# bot_schem_rev4.net
KiCad netlist of a schematic drawn in Altium Designer
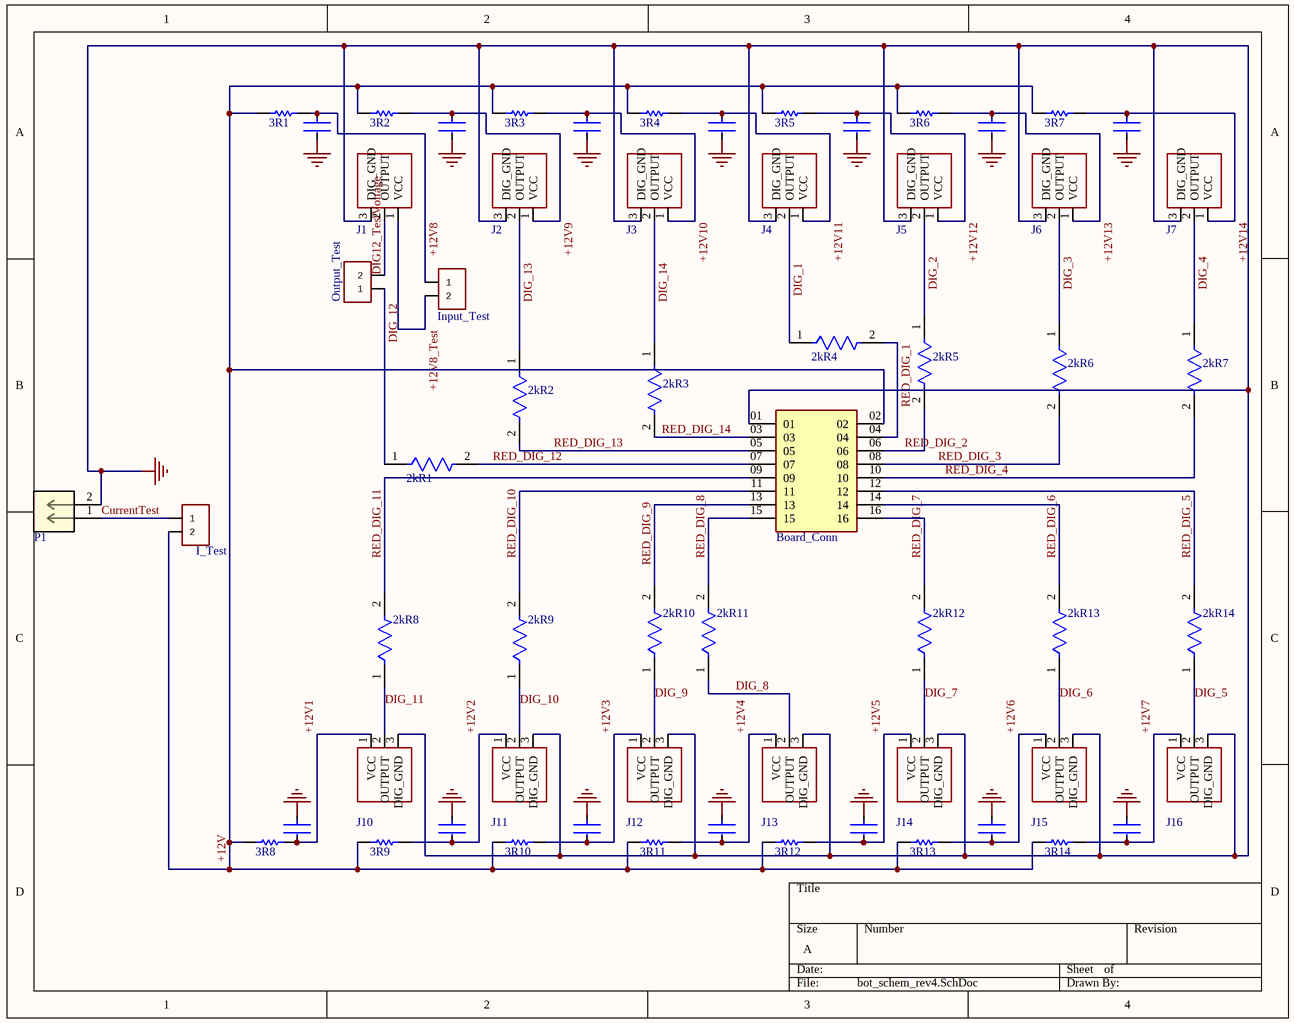
[diagram p0: bot_schem_rev4.SchDoc]

(export (version "E")
  (design (tool "Eeschema 10.0.6"))
  (components
    (comp (ref "2kR1")
      (value "CRCW06031K80FKEA")
      (footprint "2kOhm")
      (description "Res Thick Film 0603 1.8K Ohm 1% 1/10W ±100ppm/°C Molded SMD Paper T/R")
      (fields (field (name "MANUFACTURER") "Vishay") (field (name "TOLERANCE") "1%"))
      (libsource (lib "ps_schlib") (part "CRCW06031K80FKEA"))
    )
    (comp (ref "2kR2")
      (value "CRCW06031K80FKEA")
      (footprint "2kOhm")
      (description "Res Thick Film 0603 1.8K Ohm 1% 1/10W ±100ppm/°C Molded SMD Paper T/R")
      (fields (field (name "MANUFACTURER") "Vishay") (field (name "TOLERANCE") "1%"))
      (libsource (lib "ps_schlib") (part "CRCW06031K80FKEA"))
    )
    (comp (ref "2kR3")
      (value "CRCW06031K80FKEA")
      (footprint "2kOhm")
      (description "Res Thick Film 0603 1.8K Ohm 1% 1/10W ±100ppm/°C Molded SMD Paper T/R")
      (fields (field (name "MANUFACTURER") "Vishay") (field (name "TOLERANCE") "1%"))
      (libsource (lib "ps_schlib") (part "CRCW06031K80FKEA"))
    )
    (comp (ref "2kR4")
      (value "CRCW06031K80FKEA")
      (footprint "2kOhm")
      (description "Res Thick Film 0603 1.8K Ohm 1% 1/10W ±100ppm/°C Molded SMD Paper T/R")
      (fields (field (name "MANUFACTURER") "Vishay") (field (name "TOLERANCE") "1%"))
      (libsource (lib "ps_schlib") (part "CRCW06031K80FKEA"))
    )
    (comp (ref "2kR5")
      (value "CRCW06031K80FKEA")
      (footprint "2kOhm")
      (description "Res Thick Film 0603 1.8K Ohm 1% 1/10W ±100ppm/°C Molded SMD Paper T/R")
      (fields (field (name "MANUFACTURER") "Vishay") (field (name "TOLERANCE") "1%"))
      (libsource (lib "ps_schlib") (part "CRCW06031K80FKEA"))
    )
    (comp (ref "2kR6")
      (value "CRCW06031K80FKEA")
      (footprint "2kOhm")
      (description "Res Thick Film 0603 1.8K Ohm 1% 1/10W ±100ppm/°C Molded SMD Paper T/R")
      (fields (field (name "MANUFACTURER") "Vishay") (field (name "TOLERANCE") "1%"))
      (libsource (lib "ps_schlib") (part "CRCW06031K80FKEA"))
    )
    (comp (ref "2kR7")
      (value "CRCW06031K80FKEA")
      (footprint "2kOhm")
      (description "Res Thick Film 0603 1.8K Ohm 1% 1/10W ±100ppm/°C Molded SMD Paper T/R")
      (fields (field (name "MANUFACTURER") "Vishay") (field (name "TOLERANCE") "1%"))
      (libsource (lib "ps_schlib") (part "CRCW06031K80FKEA"))
    )
    (comp (ref "2kR8")
      (value "CRCW06031K80FKEA")
      (footprint "2kOhm")
      (description "Res Thick Film 0603 1.8K Ohm 1% 1/10W ±100ppm/°C Molded SMD Paper T/R")
      (fields (field (name "MANUFACTURER") "Vishay") (field (name "TOLERANCE") "1%"))
      (libsource (lib "ps_schlib") (part "CRCW06031K80FKEA"))
    )
    (comp (ref "2kR9")
      (value "CRCW06031K80FKEA")
      (footprint "2kOhm")
      (description "Res Thick Film 0603 1.8K Ohm 1% 1/10W ±100ppm/°C Molded SMD Paper T/R")
      (fields (field (name "MANUFACTURER") "Vishay") (field (name "TOLERANCE") "1%"))
      (libsource (lib "ps_schlib") (part "CRCW06031K80FKEA"))
    )
    (comp (ref "2kR10")
      (value "CRCW06031K80FKEA")
      (footprint "2kOhm")
      (description "Res Thick Film 0603 1.8K Ohm 1% 1/10W ±100ppm/°C Molded SMD Paper T/R")
      (fields (field (name "MANUFACTURER") "Vishay") (field (name "TOLERANCE") "1%"))
      (libsource (lib "ps_schlib") (part "CRCW06031K80FKEA"))
    )
    (comp (ref "2kR11")
      (value "CRCW06031K80FKEA")
      (footprint "2kOhm")
      (description "Res Thick Film 0603 1.8K Ohm 1% 1/10W ±100ppm/°C Molded SMD Paper T/R")
      (fields (field (name "MANUFACTURER") "Vishay") (field (name "TOLERANCE") "1%"))
      (libsource (lib "ps_schlib") (part "CRCW06031K80FKEA"))
    )
    (comp (ref "2kR12")
      (value "CRCW06031K80FKEA")
      (footprint "2kOhm")
      (description "Res Thick Film 0603 1.8K Ohm 1% 1/10W ±100ppm/°C Molded SMD Paper T/R")
      (fields (field (name "MANUFACTURER") "Vishay") (field (name "TOLERANCE") "1%"))
      (libsource (lib "ps_schlib") (part "CRCW06031K80FKEA"))
    )
    (comp (ref "2kR13")
      (value "CRCW06031K80FKEA")
      (footprint "2kOhm")
      (description "Res Thick Film 0603 1.8K Ohm 1% 1/10W ±100ppm/°C Molded SMD Paper T/R")
      (fields (field (name "MANUFACTURER") "Vishay") (field (name "TOLERANCE") "1%"))
      (libsource (lib "ps_schlib") (part "CRCW06031K80FKEA"))
    )
    (comp (ref "2kR14")
      (value "CRCW06031K80FKEA")
      (footprint "2kOhm")
      (description "Res Thick Film 0603 1.8K Ohm 1% 1/10W ±100ppm/°C Molded SMD Paper T/R")
      (fields (field (name "MANUFACTURER") "Vishay") (field (name "TOLERANCE") "1%"))
      (libsource (lib "ps_schlib") (part "CRCW06031K80FKEA"))
    )
    (comp (ref "3R1")
      (value "ERJ-2BQJR30X")
      (footprint "03 Ohm")
      (description "RES 0.3 OHM 5% 1/6W 0402")
      (fields (field (name "MANUFACTURER") "Panasonic") (field (name "TOLERANCE") "5%"))
      (libsource (lib "ps_schlib") (part "ERJ-2BQJR30X"))
    )
    (comp (ref "3R2")
      (value "ERJ-2BQJR30X")
      (footprint "03 Ohm")
      (description "RES 0.3 OHM 5% 1/6W 0402")
      (fields (field (name "MANUFACTURER") "Panasonic") (field (name "TOLERANCE") "5%"))
      (libsource (lib "ps_schlib") (part "ERJ-2BQJR30X"))
    )
    (comp (ref "3R3")
      (value "ERJ-2BQJR30X")
      (footprint "03 Ohm")
      (description "RES 0.3 OHM 5% 1/6W 0402")
      (fields (field (name "MANUFACTURER") "Panasonic") (field (name "TOLERANCE") "5%"))
      (libsource (lib "ps_schlib") (part "ERJ-2BQJR30X"))
    )
    (comp (ref "3R4")
      (value "ERJ-2BQJR30X")
      (footprint "03 Ohm")
      (description "RES 0.3 OHM 5% 1/6W 0402")
      (fields (field (name "MANUFACTURER") "Panasonic") (field (name "TOLERANCE") "5%"))
      (libsource (lib "ps_schlib") (part "ERJ-2BQJR30X"))
    )
    (comp (ref "3R5")
      (value "ERJ-2BQJR30X")
      (footprint "03 Ohm")
      (description "RES 0.3 OHM 5% 1/6W 0402")
      (fields (field (name "MANUFACTURER") "Panasonic") (field (name "TOLERANCE") "5%"))
      (libsource (lib "ps_schlib") (part "ERJ-2BQJR30X"))
    )
    (comp (ref "3R6")
      (value "ERJ-2BQJR30X")
      (footprint "03 Ohm")
      (description "RES 0.3 OHM 5% 1/6W 0402")
      (fields (field (name "MANUFACTURER") "Panasonic") (field (name "TOLERANCE") "5%"))
      (libsource (lib "ps_schlib") (part "ERJ-2BQJR30X"))
    )
    (comp (ref "3R7")
      (value "ERJ-2BQJR30X")
      (footprint "03 Ohm")
      (description "RES 0.3 OHM 5% 1/6W 0402")
      (fields (field (name "MANUFACTURER") "Panasonic") (field (name "TOLERANCE") "5%"))
      (libsource (lib "ps_schlib") (part "ERJ-2BQJR30X"))
    )
    (comp (ref "3R8")
      (value "ERJ-2BQJR30X")
      (footprint "03 Ohm")
      (description "RES 0.3 OHM 5% 1/6W 0402")
      (fields (field (name "MANUFACTURER") "Panasonic") (field (name "TOLERANCE") "5%"))
      (libsource (lib "ps_schlib") (part "ERJ-2BQJR30X"))
    )
    (comp (ref "3R9")
      (value "ERJ-2BQJR30X")
      (footprint "03 Ohm")
      (description "RES 0.3 OHM 5% 1/6W 0402")
      (fields (field (name "MANUFACTURER") "Panasonic") (field (name "TOLERANCE") "5%"))
      (libsource (lib "ps_schlib") (part "ERJ-2BQJR30X"))
    )
    (comp (ref "3R10")
      (value "ERJ-2BQJR30X")
      (footprint "03 Ohm")
      (description "RES 0.3 OHM 5% 1/6W 0402")
      (fields (field (name "MANUFACTURER") "Panasonic") (field (name "TOLERANCE") "5%"))
      (libsource (lib "ps_schlib") (part "ERJ-2BQJR30X"))
    )
    (comp (ref "3R11")
      (value "ERJ-2BQJR30X")
      (footprint "03 Ohm")
      (description "RES 0.3 OHM 5% 1/6W 0402")
      (fields (field (name "MANUFACTURER") "Panasonic") (field (name "TOLERANCE") "5%"))
      (libsource (lib "ps_schlib") (part "ERJ-2BQJR30X"))
    )
    (comp (ref "3R12")
      (value "ERJ-2BQJR30X")
      (footprint "03 Ohm")
      (description "RES 0.3 OHM 5% 1/6W 0402")
      (fields (field (name "MANUFACTURER") "Panasonic") (field (name "TOLERANCE") "5%"))
      (libsource (lib "ps_schlib") (part "ERJ-2BQJR30X"))
    )
    (comp (ref "3R13")
      (value "ERJ-2BQJR30X")
      (footprint "03 Ohm")
      (description "RES 0.3 OHM 5% 1/6W 0402")
      (fields (field (name "MANUFACTURER") "Panasonic") (field (name "TOLERANCE") "5%"))
      (libsource (lib "ps_schlib") (part "ERJ-2BQJR30X"))
    )
    (comp (ref "3R14")
      (value "ERJ-2BQJR30X")
      (footprint "03 Ohm")
      (description "RES 0.3 OHM 5% 1/6W 0402")
      (fields (field (name "MANUFACTURER") "Panasonic") (field (name "TOLERANCE") "5%"))
      (libsource (lib "ps_schlib") (part "ERJ-2BQJR30X"))
    )
    (comp (ref "Board_Conn")
      (value "HW-08-11-F-D-511-SM")
      (footprint "16 pin receiver")
      (libsource (lib "ps_schlib") (part "HW-08-11-F-D-507-SM"))
    )
    (comp (ref "C1")
      (value "C0805C104K5RACTU")
      (footprint "100nF")
      (description "Cap Ceramic 0.1uF 50V X7R 10% SMD 2.0 x 1.2 mm 125 C Paper T/R")
      (fields (field (name "MANUFACTURER") "KEMET") (field (name "TOLERANCE") "10%"))
      (libsource (lib "ps_schlib") (part "C0805C104K5RACTU"))
    )
    (comp (ref "C2")
      (value "C0805C104K5RACTU")
      (footprint "100nF")
      (description "Cap Ceramic 0.1uF 50V X7R 10% SMD 2.0 x 1.2 mm 125 C Paper T/R")
      (fields (field (name "MANUFACTURER") "KEMET") (field (name "TOLERANCE") "10%"))
      (libsource (lib "ps_schlib") (part "C0805C104K5RACTU"))
    )
    (comp (ref "C3")
      (value "C0805C104K5RACTU")
      (footprint "100nF")
      (description "Cap Ceramic 0.1uF 50V X7R 10% SMD 2.0 x 1.2 mm 125 C Paper T/R")
      (fields (field (name "MANUFACTURER") "KEMET") (field (name "TOLERANCE") "10%"))
      (libsource (lib "ps_schlib") (part "C0805C104K5RACTU"))
    )
    (comp (ref "C4")
      (value "C0805C104K5RACTU")
      (footprint "100nF")
      (description "Cap Ceramic 0.1uF 50V X7R 10% SMD 2.0 x 1.2 mm 125 C Paper T/R")
      (fields (field (name "MANUFACTURER") "KEMET") (field (name "TOLERANCE") "10%"))
      (libsource (lib "ps_schlib") (part "C0805C104K5RACTU"))
    )
    (comp (ref "C5")
      (value "C0805C104K5RACTU")
      (footprint "100nF")
      (description "Cap Ceramic 0.1uF 50V X7R 10% SMD 2.0 x 1.2 mm 125 C Paper T/R")
      (fields (field (name "MANUFACTURER") "KEMET") (field (name "TOLERANCE") "10%"))
      (libsource (lib "ps_schlib") (part "C0805C104K5RACTU"))
    )
    (comp (ref "C6")
      (value "C0805C104K5RACTU")
      (footprint "100nF")
      (description "Cap Ceramic 0.1uF 50V X7R 10% SMD 2.0 x 1.2 mm 125 C Paper T/R")
      (fields (field (name "MANUFACTURER") "KEMET") (field (name "TOLERANCE") "10%"))
      (libsource (lib "ps_schlib") (part "C0805C104K5RACTU"))
    )
    (comp (ref "C7")
      (value "C0805C104K5RACTU")
      (footprint "100nF")
      (description "Cap Ceramic 0.1uF 50V X7R 10% SMD 2.0 x 1.2 mm 125 C Paper T/R")
      (fields (field (name "MANUFACTURER") "KEMET") (field (name "TOLERANCE") "10%"))
      (libsource (lib "ps_schlib") (part "C0805C104K5RACTU"))
    )
    (comp (ref "C8")
      (value "C0805C104K5RACTU")
      (footprint "100nF")
      (description "Cap Ceramic 0.1uF 50V X7R 10% SMD 2.0 x 1.2 mm 125 C Paper T/R")
      (fields (field (name "MANUFACTURER") "KEMET") (field (name "TOLERANCE") "10%"))
      (libsource (lib "ps_schlib") (part "C0805C104K5RACTU"))
    )
    (comp (ref "C9")
      (value "C0805C104K5RACTU")
      (footprint "100nF")
      (description "Cap Ceramic 0.1uF 50V X7R 10% SMD 2.0 x 1.2 mm 125 C Paper T/R")
      (fields (field (name "MANUFACTURER") "KEMET") (field (name "TOLERANCE") "10%"))
      (libsource (lib "ps_schlib") (part "C0805C104K5RACTU"))
    )
    (comp (ref "C10")
      (value "C0805C104K5RACTU")
      (footprint "100nF")
      (description "Cap Ceramic 0.1uF 50V X7R 10% SMD 2.0 x 1.2 mm 125 C Paper T/R")
      (fields (field (name "MANUFACTURER") "KEMET") (field (name "TOLERANCE") "10%"))
      (libsource (lib "ps_schlib") (part "C0805C104K5RACTU"))
    )
    (comp (ref "C11")
      (value "C0805C104K5RACTU")
      (footprint "100nF")
      (description "Cap Ceramic 0.1uF 50V X7R 10% SMD 2.0 x 1.2 mm 125 C Paper T/R")
      (fields (field (name "MANUFACTURER") "KEMET") (field (name "TOLERANCE") "10%"))
      (libsource (lib "ps_schlib") (part "C0805C104K5RACTU"))
    )
    (comp (ref "C12")
      (value "C0805C104K5RACTU")
      (footprint "100nF")
      (description "Cap Ceramic 0.1uF 50V X7R 10% SMD 2.0 x 1.2 mm 125 C Paper T/R")
      (fields (field (name "MANUFACTURER") "KEMET") (field (name "TOLERANCE") "10%"))
      (libsource (lib "ps_schlib") (part "C0805C104K5RACTU"))
    )
    (comp (ref "C13")
      (value "C0805C104K5RACTU")
      (footprint "100nF")
      (description "Cap Ceramic 0.1uF 50V X7R 10% SMD 2.0 x 1.2 mm 125 C Paper T/R")
      (fields (field (name "MANUFACTURER") "KEMET") (field (name "TOLERANCE") "10%"))
      (libsource (lib "ps_schlib") (part "C0805C104K5RACTU"))
    )
    (comp (ref "C14")
      (value "C0805C104K5RACTU")
      (footprint "100nF")
      (description "Cap Ceramic 0.1uF 50V X7R 10% SMD 2.0 x 1.2 mm 125 C Paper T/R")
      (fields (field (name "MANUFACTURER") "KEMET") (field (name "TOLERANCE") "10%"))
      (libsource (lib "ps_schlib") (part "C0805C104K5RACTU"))
    )
    (comp (ref "Input_Test")
      (value "PRPC001DFAN-RC")
      (footprint "PRPC001DFAN-RC")
      (description "Conn Header Vert 2POS")
      (fields (field (name "MANUFACTURER") "Sullins"))
      (libsource (lib "ps_schlib") (part "PRPC001DFAN-RC"))
    )
    (comp (ref "I_Test")
      (value "PRPC001DFAN-RC")
      (footprint "PRPC001DFAN-RC")
      (description "Conn Header Vert 2POS")
      (fields (field (name "MANUFACTURER") "Sullins"))
      (libsource (lib "ps_schlib") (part "PRPC001DFAN-RC"))
    )
    (comp (ref "J1")
      (value "IF-D95T")
      (footprint "IF-D95")
      (description "DETECTOR PHOTOLOGIC TTL/CMOS")
      (fields (field (name "MANUFACTURER") "Industrial Fiber Optics"))
      (libsource (lib "ps_schlib") (part "IF-D95T"))
    )
    (comp (ref "J2")
      (value "IF-D95T")
      (footprint "IF-D95")
      (description "DETECTOR PHOTOLOGIC TTL/CMOS")
      (fields (field (name "MANUFACTURER") "Industrial Fiber Optics"))
      (libsource (lib "ps_schlib") (part "IF-D95T"))
    )
    (comp (ref "J3")
      (value "IF-D95T")
      (footprint "IF-D95")
      (description "DETECTOR PHOTOLOGIC TTL/CMOS")
      (fields (field (name "MANUFACTURER") "Industrial Fiber Optics"))
      (libsource (lib "ps_schlib") (part "IF-D95T"))
    )
    (comp (ref "J4")
      (value "IF-D95T")
      (footprint "IF-D95")
      (description "DETECTOR PHOTOLOGIC TTL/CMOS")
      (fields (field (name "MANUFACTURER") "Industrial Fiber Optics"))
      (libsource (lib "ps_schlib") (part "IF-D95T"))
    )
    (comp (ref "J5")
      (value "IF-D95T")
      (footprint "IF-D95")
      (description "DETECTOR PHOTOLOGIC TTL/CMOS")
      (fields (field (name "MANUFACTURER") "Industrial Fiber Optics"))
      (libsource (lib "ps_schlib") (part "IF-D95T"))
    )
    (comp (ref "J6")
      (value "IF-D95T")
      (footprint "IF-D95")
      (description "DETECTOR PHOTOLOGIC TTL/CMOS")
      (fields (field (name "MANUFACTURER") "Industrial Fiber Optics"))
      (libsource (lib "ps_schlib") (part "IF-D95T"))
    )
    (comp (ref "J7")
      (value "IF-D95T")
      (footprint "IF-D95")
      (description "DETECTOR PHOTOLOGIC TTL/CMOS")
      (fields (field (name "MANUFACTURER") "Industrial Fiber Optics"))
      (libsource (lib "ps_schlib") (part "IF-D95T"))
    )
    (comp (ref "J10")
      (value "IF-D95T")
      (footprint "IF-D95")
      (description "DETECTOR PHOTOLOGIC TTL/CMOS")
      (fields (field (name "MANUFACTURER") "Industrial Fiber Optics"))
      (libsource (lib "ps_schlib") (part "IF-D95T"))
    )
    (comp (ref "J11")
      (value "IF-D95T")
      (footprint "IF-D95")
      (description "DETECTOR PHOTOLOGIC TTL/CMOS")
      (fields (field (name "MANUFACTURER") "Industrial Fiber Optics"))
      (libsource (lib "ps_schlib") (part "IF-D95T"))
    )
    (comp (ref "J12")
      (value "IF-D95T")
      (footprint "IF-D95")
      (description "DETECTOR PHOTOLOGIC TTL/CMOS")
      (fields (field (name "MANUFACTURER") "Industrial Fiber Optics"))
      (libsource (lib "ps_schlib") (part "IF-D95T"))
    )
    (comp (ref "J13")
      (value "IF-D95T")
      (footprint "IF-D95")
      (description "DETECTOR PHOTOLOGIC TTL/CMOS")
      (fields (field (name "MANUFACTURER") "Industrial Fiber Optics"))
      (libsource (lib "ps_schlib") (part "IF-D95T"))
    )
    (comp (ref "J14")
      (value "IF-D95T")
      (footprint "IF-D95")
      (description "DETECTOR PHOTOLOGIC TTL/CMOS")
      (fields (field (name "MANUFACTURER") "Industrial Fiber Optics"))
      (libsource (lib "ps_schlib") (part "IF-D95T"))
    )
    (comp (ref "J15")
      (value "IF-D95T")
      (footprint "IF-D95")
      (description "DETECTOR PHOTOLOGIC TTL/CMOS")
      (fields (field (name "MANUFACTURER") "Industrial Fiber Optics"))
      (libsource (lib "ps_schlib") (part "IF-D95T"))
    )
    (comp (ref "J16")
      (value "IF-D95T")
      (footprint "IF-D95")
      (description "DETECTOR PHOTOLOGIC TTL/CMOS")
      (fields (field (name "MANUFACTURER") "Industrial Fiber Optics"))
      (libsource (lib "ps_schlib") (part "IF-D95T"))
    )
    (comp (ref "Output_Test")
      (value "PRPC001DFAN-RC")
      (footprint "PRPC001DFAN-RC")
      (description "Conn Header Vert 2POS")
      (fields (field (name "MANUFACTURER") "Sullins"))
      (libsource (lib "ps_schlib") (part "PRPC001DFAN-RC"))
    )
    (comp (ref "P1")
      (value "1054311102")
      (footprint "CONN_1054311102_MOL")
      (fields (field (name "MANUFACTURER") "Molex"))
      (libsource (lib "ps_schlib") (part "1054311102"))
    )
  )
  (nets
    (net (code "1") (name "/+12V") (class "Default")
      (node (ref "3R1") (pin "1") (pinfunction "1_1") (pintype "passive"))
      (node (ref "3R10") (pin "1") (pinfunction "1_1") (pintype "passive"))
      (node (ref "3R11") (pin "1") (pinfunction "1_1") (pintype "passive"))
      (node (ref "3R12") (pin "1") (pinfunction "1_1") (pintype "passive"))
      (node (ref "3R13") (pin "1") (pinfunction "1_1") (pintype "passive"))
      (node (ref "3R14") (pin "1") (pinfunction "1_1") (pintype "passive"))
      (node (ref "3R2") (pin "1") (pinfunction "1_1") (pintype "passive"))
      (node (ref "3R3") (pin "1") (pinfunction "1_1") (pintype "passive"))
      (node (ref "3R4") (pin "1") (pinfunction "1_1") (pintype "passive"))
      (node (ref "3R5") (pin "1") (pinfunction "1_1") (pintype "passive"))
      (node (ref "3R6") (pin "1") (pinfunction "1_1") (pintype "passive"))
      (node (ref "3R7") (pin "1") (pinfunction "1_1") (pintype "passive"))
      (node (ref "3R8") (pin "1") (pinfunction "1_1") (pintype "passive"))
      (node (ref "3R9") (pin "1") (pinfunction "1_1") (pintype "passive"))
      (node (ref "Board_Conn") (pin "02") (pinfunction "02_02") (pintype "passive"))
      (node (ref "I_Test") (pin "2") (pinfunction "2_2") (pintype "passive"))
    )
    (net (code "2") (name "/+12V1") (class "Default")
      (node (ref "3R8") (pin "2") (pinfunction "2_2") (pintype "passive"))
      (node (ref "C8") (pin "2") (pinfunction "2_2") (pintype "passive"))
      (node (ref "J10") (pin "1") (pinfunction "VCC_1") (pintype "passive"))
    )
    (net (code "3") (name "/+12V2") (class "Default")
      (node (ref "3R9") (pin "2") (pinfunction "2_2") (pintype "passive"))
      (node (ref "C9") (pin "2") (pinfunction "2_2") (pintype "passive"))
      (node (ref "J11") (pin "1") (pinfunction "VCC_1") (pintype "passive"))
    )
    (net (code "4") (name "/+12V3") (class "Default")
      (node (ref "3R10") (pin "2") (pinfunction "2_2") (pintype "passive"))
      (node (ref "C10") (pin "2") (pinfunction "2_2") (pintype "passive"))
      (node (ref "J12") (pin "1") (pinfunction "VCC_1") (pintype "passive"))
    )
    (net (code "5") (name "/+12V4") (class "Default")
      (node (ref "3R11") (pin "2") (pinfunction "2_2") (pintype "passive"))
      (node (ref "C11") (pin "2") (pinfunction "2_2") (pintype "passive"))
      (node (ref "J13") (pin "1") (pinfunction "VCC_1") (pintype "passive"))
    )
    (net (code "6") (name "/+12V5") (class "Default")
      (node (ref "3R12") (pin "2") (pinfunction "2_2") (pintype "passive"))
      (node (ref "C12") (pin "2") (pinfunction "2_2") (pintype "passive"))
      (node (ref "J14") (pin "1") (pinfunction "VCC_1") (pintype "passive"))
    )
    (net (code "7") (name "/+12V6") (class "Default")
      (node (ref "3R13") (pin "2") (pinfunction "2_2") (pintype "passive"))
      (node (ref "C13") (pin "2") (pinfunction "2_2") (pintype "passive"))
      (node (ref "J15") (pin "1") (pinfunction "VCC_1") (pintype "passive"))
    )
    (net (code "8") (name "/+12V7") (class "Default")
      (node (ref "3R14") (pin "2") (pinfunction "2_2") (pintype "passive"))
      (node (ref "C14") (pin "2") (pinfunction "2_2") (pintype "passive"))
      (node (ref "J16") (pin "1") (pinfunction "VCC_1") (pintype "passive"))
    )
    (net (code "9") (name "/+12V8") (class "Default")
      (node (ref "3R1") (pin "2") (pinfunction "2_2") (pintype "passive"))
      (node (ref "C1") (pin "1") (pinfunction "1_1") (pintype "passive"))
      (node (ref "Input_Test") (pin "1") (pinfunction "1_1") (pintype "passive"))
    )
    (net (code "10") (name "/+12V8_Test") (class "Default")
      (node (ref "Input_Test") (pin "2") (pinfunction "2_2") (pintype "passive"))
      (node (ref "J1") (pin "1") (pinfunction "VCC_1") (pintype "passive"))
    )
    (net (code "11") (name "/+12V9") (class "Default")
      (node (ref "3R2") (pin "2") (pinfunction "2_2") (pintype "passive"))
      (node (ref "C2") (pin "1") (pinfunction "1_1") (pintype "passive"))
      (node (ref "J2") (pin "1") (pinfunction "VCC_1") (pintype "passive"))
    )
    (net (code "12") (name "/+12V10") (class "Default")
      (node (ref "3R3") (pin "2") (pinfunction "2_2") (pintype "passive"))
      (node (ref "C3") (pin "1") (pinfunction "1_1") (pintype "passive"))
      (node (ref "J3") (pin "1") (pinfunction "VCC_1") (pintype "passive"))
    )
    (net (code "13") (name "/+12V11") (class "Default")
      (node (ref "3R4") (pin "2") (pinfunction "2_2") (pintype "passive"))
      (node (ref "C4") (pin "1") (pinfunction "1_1") (pintype "passive"))
      (node (ref "J4") (pin "1") (pinfunction "VCC_1") (pintype "passive"))
    )
    (net (code "14") (name "/+12V12") (class "Default")
      (node (ref "3R5") (pin "2") (pinfunction "2_2") (pintype "passive"))
      (node (ref "C5") (pin "1") (pinfunction "1_1") (pintype "passive"))
      (node (ref "J5") (pin "1") (pinfunction "VCC_1") (pintype "passive"))
    )
    (net (code "15") (name "/+12V13") (class "Default")
      (node (ref "3R6") (pin "2") (pinfunction "2_2") (pintype "passive"))
      (node (ref "C6") (pin "1") (pinfunction "1_1") (pintype "passive"))
      (node (ref "J6") (pin "1") (pinfunction "VCC_1") (pintype "passive"))
    )
    (net (code "16") (name "/+12V14") (class "Default")
      (node (ref "3R7") (pin "2") (pinfunction "2_2") (pintype "passive"))
      (node (ref "C7") (pin "1") (pinfunction "1_1") (pintype "passive"))
      (node (ref "J7") (pin "1") (pinfunction "VCC_1") (pintype "passive"))
    )
    (net (code "18") (name "/CurrentTest") (class "Default")
      (node (ref "I_Test") (pin "1") (pinfunction "1_1") (pintype "passive"))
      (node (ref "P1") (pin "1") (pinfunction "1_1") (pintype "passive"))
    )
    (net (code "19") (name "/DIG12_TestVoltage") (class "Default")
      (node (ref "J1") (pin "2") (pinfunction "OUTPUT_2") (pintype "passive"))
      (node (ref "Output_Test") (pin "2") (pinfunction "2_2") (pintype "passive"))
    )
    (net (code "20") (name "/DIG_1") (class "Default")
      (node (ref "2kR4") (pin "1") (pinfunction "1_1") (pintype "passive"))
      (node (ref "J4") (pin "2") (pinfunction "OUTPUT_2") (pintype "passive"))
    )
    (net (code "21") (name "/DIG_2") (class "Default")
      (node (ref "2kR5") (pin "1") (pinfunction "1_1") (pintype "passive"))
      (node (ref "J5") (pin "2") (pinfunction "OUTPUT_2") (pintype "passive"))
    )
    (net (code "22") (name "/DIG_3") (class "Default")
      (node (ref "2kR6") (pin "1") (pinfunction "1_1") (pintype "passive"))
      (node (ref "J6") (pin "2") (pinfunction "OUTPUT_2") (pintype "passive"))
    )
    (net (code "23") (name "/DIG_4") (class "Default")
      (node (ref "2kR7") (pin "1") (pinfunction "1_1") (pintype "passive"))
      (node (ref "J7") (pin "2") (pinfunction "OUTPUT_2") (pintype "passive"))
    )
    (net (code "24") (name "/DIG_5") (class "Default")
      (node (ref "2kR14") (pin "1") (pinfunction "1_1") (pintype "passive"))
      (node (ref "J16") (pin "2") (pinfunction "OUTPUT_2") (pintype "passive"))
    )
    (net (code "25") (name "/DIG_6") (class "Default")
      (node (ref "2kR13") (pin "1") (pinfunction "1_1") (pintype "passive"))
      (node (ref "J15") (pin "2") (pinfunction "OUTPUT_2") (pintype "passive"))
    )
    (net (code "26") (name "/DIG_7") (class "Default")
      (node (ref "2kR12") (pin "1") (pinfunction "1_1") (pintype "passive"))
      (node (ref "J14") (pin "2") (pinfunction "OUTPUT_2") (pintype "passive"))
    )
    (net (code "27") (name "/DIG_8") (class "Default")
      (node (ref "2kR11") (pin "1") (pinfunction "1_1") (pintype "passive"))
      (node (ref "J13") (pin "2") (pinfunction "OUTPUT_2") (pintype "passive"))
    )
    (net (code "28") (name "/DIG_9") (class "Default")
      (node (ref "2kR10") (pin "1") (pinfunction "1_1") (pintype "passive"))
      (node (ref "J12") (pin "2") (pinfunction "OUTPUT_2") (pintype "passive"))
    )
    (net (code "29") (name "/DIG_10") (class "Default")
      (node (ref "2kR9") (pin "1") (pinfunction "1_1") (pintype "passive"))
      (node (ref "J11") (pin "2") (pinfunction "OUTPUT_2") (pintype "passive"))
    )
    (net (code "30") (name "/DIG_11") (class "Default")
      (node (ref "2kR8") (pin "1") (pinfunction "1_1") (pintype "passive"))
      (node (ref "J10") (pin "2") (pinfunction "OUTPUT_2") (pintype "passive"))
    )
    (net (code "31") (name "/DIG_12") (class "Default")
      (node (ref "2kR1") (pin "1") (pinfunction "1_1") (pintype "passive"))
      (node (ref "Output_Test") (pin "1") (pinfunction "1_1") (pintype "passive"))
    )
    (net (code "32") (name "/DIG_13") (class "Default")
      (node (ref "2kR2") (pin "1") (pinfunction "1_1") (pintype "passive"))
      (node (ref "J2") (pin "2") (pinfunction "OUTPUT_2") (pintype "passive"))
    )
    (net (code "33") (name "/DIG_14") (class "Default")
      (node (ref "2kR3") (pin "1") (pinfunction "1_1") (pintype "passive"))
      (node (ref "J3") (pin "2") (pinfunction "OUTPUT_2") (pintype "passive"))
    )
    (net (code "34") (name "/RED_DIG_1") (class "Default")
      (node (ref "2kR4") (pin "2") (pinfunction "2_2") (pintype "passive"))
      (node (ref "Board_Conn") (pin "04") (pinfunction "04_04") (pintype "passive"))
    )
    (net (code "35") (name "/RED_DIG_2") (class "Default")
      (node (ref "2kR5") (pin "2") (pinfunction "2_2") (pintype "passive"))
      (node (ref "Board_Conn") (pin "06") (pinfunction "06_06") (pintype "passive"))
    )
    (net (code "36") (name "/RED_DIG_3") (class "Default")
      (node (ref "2kR6") (pin "2") (pinfunction "2_2") (pintype "passive"))
      (node (ref "Board_Conn") (pin "08") (pinfunction "08_08") (pintype "passive"))
    )
    (net (code "37") (name "/RED_DIG_4") (class "Default")
      (node (ref "2kR7") (pin "2") (pinfunction "2_2") (pintype "passive"))
      (node (ref "Board_Conn") (pin "10") (pinfunction "10_10") (pintype "passive"))
    )
    (net (code "38") (name "/RED_DIG_5") (class "Default")
      (node (ref "2kR14") (pin "2") (pinfunction "2_2") (pintype "passive"))
      (node (ref "Board_Conn") (pin "12") (pinfunction "12_12") (pintype "passive"))
    )
    (net (code "39") (name "/RED_DIG_6") (class "Default")
      (node (ref "2kR13") (pin "2") (pinfunction "2_2") (pintype "passive"))
      (node (ref "Board_Conn") (pin "14") (pinfunction "14_14") (pintype "passive"))
    )
    (net (code "40") (name "/RED_DIG_7") (class "Default")
      (node (ref "2kR12") (pin "2") (pinfunction "2_2") (pintype "passive"))
      (node (ref "Board_Conn") (pin "16") (pinfunction "16_16") (pintype "passive"))
    )
    (net (code "41") (name "/RED_DIG_8") (class "Default")
      (node (ref "2kR11") (pin "2") (pinfunction "2_2") (pintype "passive"))
      (node (ref "Board_Conn") (pin "15") (pinfunction "15_15") (pintype "passive"))
    )
    (net (code "42") (name "/RED_DIG_9") (class "Default")
      (node (ref "2kR10") (pin "2") (pinfunction "2_2") (pintype "passive"))
      (node (ref "Board_Conn") (pin "13") (pinfunction "13_13") (pintype "passive"))
    )
    (net (code "43") (name "/RED_DIG_10") (class "Default")
      (node (ref "2kR9") (pin "2") (pinfunction "2_2") (pintype "passive"))
      (node (ref "Board_Conn") (pin "11") (pinfunction "11_11") (pintype "passive"))
    )
    (net (code "44") (name "/RED_DIG_11") (class "Default")
      (node (ref "2kR8") (pin "2") (pinfunction "2_2") (pintype "passive"))
      (node (ref "Board_Conn") (pin "09") (pinfunction "09_09") (pintype "passive"))
    )
    (net (code "45") (name "/RED_DIG_12") (class "Default")
      (node (ref "2kR1") (pin "2") (pinfunction "2_2") (pintype "passive"))
      (node (ref "Board_Conn") (pin "07") (pinfunction "07_07") (pintype "passive"))
    )
    (net (code "46") (name "/RED_DIG_13") (class "Default")
      (node (ref "2kR2") (pin "2") (pinfunction "2_2") (pintype "passive"))
      (node (ref "Board_Conn") (pin "05") (pinfunction "05_05") (pintype "passive"))
    )
    (net (code "47") (name "/RED_DIG_14") (class "Default")
      (node (ref "2kR3") (pin "2") (pinfunction "2_2") (pintype "passive"))
      (node (ref "Board_Conn") (pin "03") (pinfunction "03_03") (pintype "passive"))
    )
    (net (code "48") (name "GND") (class "Default")
      (node (ref "Board_Conn") (pin "01") (pinfunction "01_01") (pintype "passive"))
      (node (ref "C1") (pin "2") (pinfunction "2_2") (pintype "passive"))
      (node (ref "C10") (pin "1") (pinfunction "1_1") (pintype "passive"))
      (node (ref "C11") (pin "1") (pinfunction "1_1") (pintype "passive"))
      (node (ref "C12") (pin "1") (pinfunction "1_1") (pintype "passive"))
      (node (ref "C13") (pin "1") (pinfunction "1_1") (pintype "passive"))
      (node (ref "C14") (pin "1") (pinfunction "1_1") (pintype "passive"))
      (node (ref "C2") (pin "2") (pinfunction "2_2") (pintype "passive"))
      (node (ref "C3") (pin "2") (pinfunction "2_2") (pintype "passive"))
      (node (ref "C4") (pin "2") (pinfunction "2_2") (pintype "passive"))
      (node (ref "C5") (pin "2") (pinfunction "2_2") (pintype "passive"))
      (node (ref "C6") (pin "2") (pinfunction "2_2") (pintype "passive"))
      (node (ref "C7") (pin "2") (pinfunction "2_2") (pintype "passive"))
      (node (ref "C8") (pin "1") (pinfunction "1_1") (pintype "passive"))
      (node (ref "C9") (pin "1") (pinfunction "1_1") (pintype "passive"))
      (node (ref "J1") (pin "3") (pinfunction "DIG_GND_3") (pintype "passive"))
      (node (ref "J10") (pin "3") (pinfunction "DIG_GND_3") (pintype "passive"))
      (node (ref "J11") (pin "3") (pinfunction "DIG_GND_3") (pintype "passive"))
      (node (ref "J12") (pin "3") (pinfunction "DIG_GND_3") (pintype "passive"))
      (node (ref "J13") (pin "3") (pinfunction "DIG_GND_3") (pintype "passive"))
      (node (ref "J14") (pin "3") (pinfunction "DIG_GND_3") (pintype "passive"))
      (node (ref "J15") (pin "3") (pinfunction "DIG_GND_3") (pintype "passive"))
      (node (ref "J16") (pin "3") (pinfunction "DIG_GND_3") (pintype "passive"))
      (node (ref "J2") (pin "3") (pinfunction "DIG_GND_3") (pintype "passive"))
      (node (ref "J3") (pin "3") (pinfunction "DIG_GND_3") (pintype "passive"))
      (node (ref "J4") (pin "3") (pinfunction "DIG_GND_3") (pintype "passive"))
      (node (ref "J5") (pin "3") (pinfunction "DIG_GND_3") (pintype "passive"))
      (node (ref "J6") (pin "3") (pinfunction "DIG_GND_3") (pintype "passive"))
      (node (ref "J7") (pin "3") (pinfunction "DIG_GND_3") (pintype "passive"))
      (node (ref "P1") (pin "2") (pinfunction "2_2") (pintype "passive"))
    )
  )
)
